# 3_-STM32F103_Debugger.net
KiCad netlist of a schematic drawn in Altium Designer
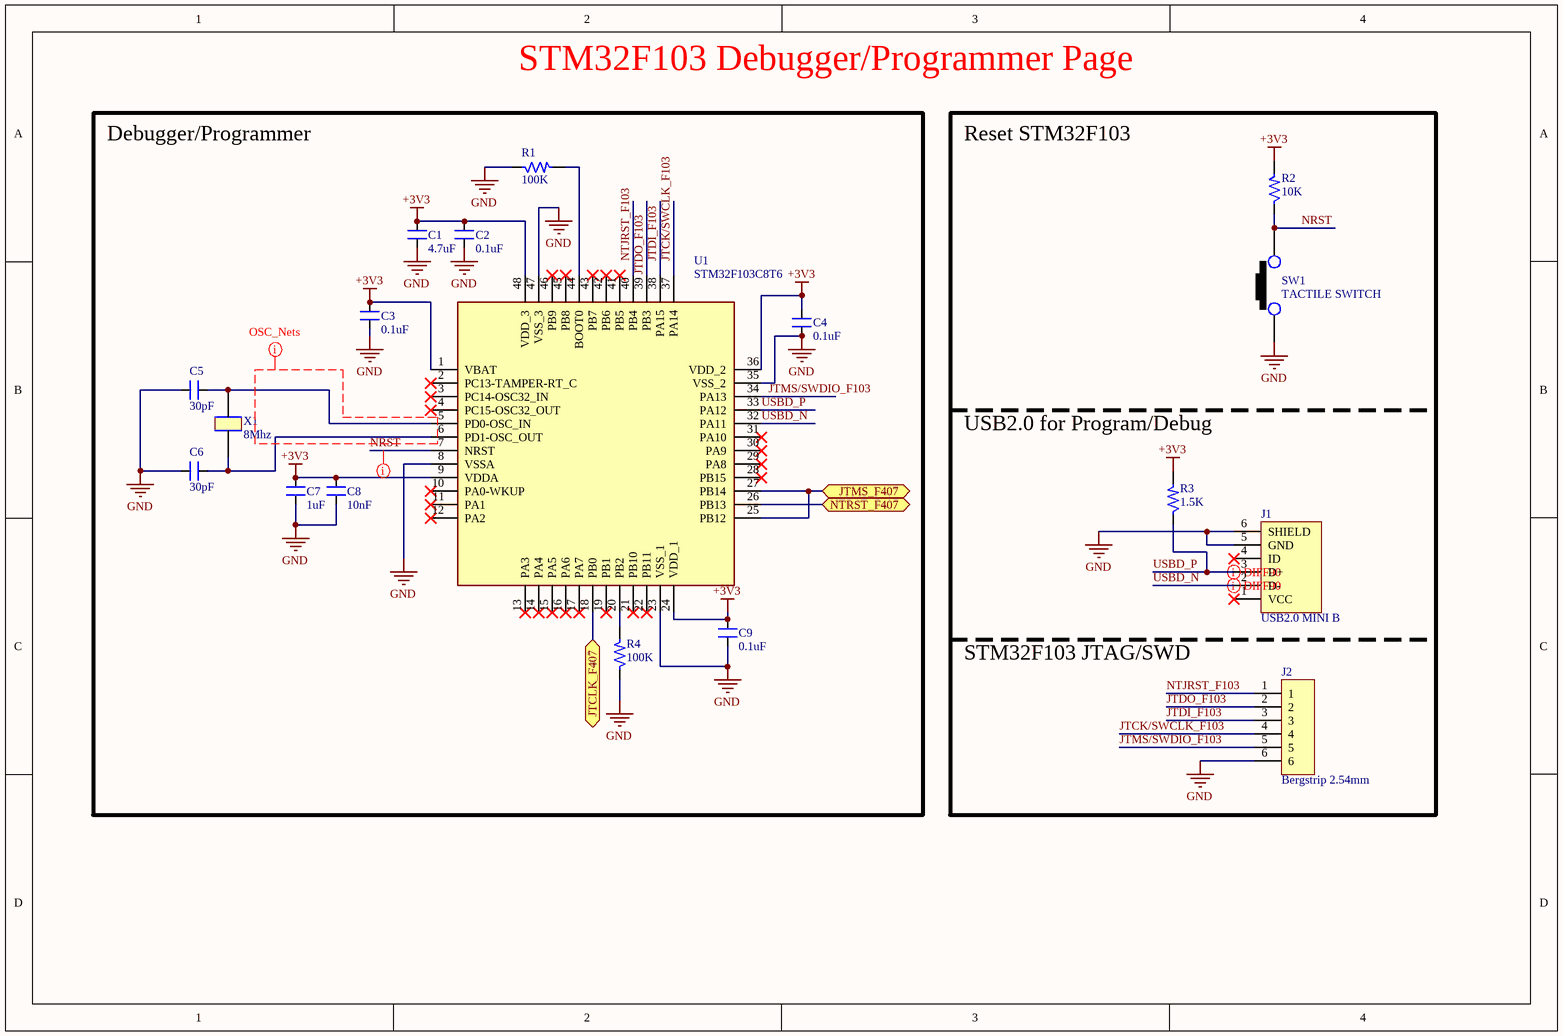
[diagram p0: [3]-STM32F103 Debugger.SchDoc]

(export (version "E")
  (design (tool "Eeschema 10.0.6"))
  (components
    (comp (ref "C1")
      (value "4.7uF")
      (footprint "CAP_0805")
      (description "4.7µF ±10% 50V Ceramic Capacitor X5R 0805 (2012 Metric)")
      (fields
        (field (name "MANUFACTURER") "Yageo")
        (field (name "MANUFACTURER PART NUMBER") "GRM21BR61H475KE51L")
      )
      (libsource (lib "ESTEEMPCBLIB") (part "CAP_4.7uF-50V-10%-0805"))
    )
    (comp (ref "C2")
      (value "0.1uF")
      (footprint "CAP_0805")
      (description "0.1µF ±10% 50V Ceramic Capacitor X7R 0805 (2012 Metric)")
      (fields
        (field (name "MANUFACTURER") "Samsung")
        (field (name "MANUFACTURER PART NUMBER") "CL21B104KBCNNNC")
      )
      (libsource (lib "ESTEEMPCBLIB") (part "CAP_0.1uF-50V-10%-0805"))
    )
    (comp (ref "C3")
      (value "0.1uF")
      (footprint "CAP_0805")
      (description "0.1µF ±10% 50V Ceramic Capacitor X7R 0805 (2012 Metric)")
      (fields
        (field (name "MANUFACTURER") "Samsung")
        (field (name "MANUFACTURER PART NUMBER") "CL21B104KBCNNNC")
      )
      (libsource (lib "ESTEEMPCBLIB") (part "CAP_0.1uF-50V-10%-0805"))
    )
    (comp (ref "C4")
      (value "0.1uF")
      (footprint "CAP_0805")
      (description "0.1µF ±10% 50V Ceramic Capacitor X7R 0805 (2012 Metric)")
      (fields
        (field (name "MANUFACTURER") "Samsung")
        (field (name "MANUFACTURER PART NUMBER") "CL21B104KBCNNNC")
      )
      (libsource (lib "ESTEEMPCBLIB") (part "CAP_0.1uF-50V-10%-0805"))
    )
    (comp (ref "C5")
      (value "30pF")
      (footprint "CAP_0805")
      (description "±10% 50V Ceramic Capacitor C0G, NP0 0805 (2012 Metric)")
      (fields
        (field (name "MANUFACTURER PART NUMBER") "C0805C300K5GAC7800")
        (field (name "MANUFACTURER") "KEMET")
      )
      (libsource (lib "ESTEEMPCBLIB") (part "CAP_30pF-50V-10%-0805"))
    )
    (comp (ref "C6")
      (value "30pF")
      (footprint "CAP_0805")
      (description "±10% 50V Ceramic Capacitor C0G, NP0 0805 (2012 Metric)")
      (fields
        (field (name "MANUFACTURER PART NUMBER") "C0805C300K5GAC7800")
        (field (name "MANUFACTURER") "KEMET")
      )
      (libsource (lib "ESTEEMPCBLIB") (part "CAP_30pF-50V-10%-0805"))
    )
    (comp (ref "C7")
      (value "1uF")
      (footprint "CAP_0805")
      (description "1µF ±5% 50V Ceramic Capacitor X7R 0805 (2012 Metric)")
      (fields
        (field (name "MANUFACTURER") "Samsung")
        (field (name "MANUFACTURER PART NUMBER") "CC0805JKX7R9BB105")
      )
      (libsource (lib "ESTEEMPCBLIB") (part "CAP_1uF-50V-5%-0805"))
    )
    (comp (ref "C8")
      (value "10nF")
      (footprint "CAP_0805")
      (description "10000pF ±10% 50V Ceramic Capacitor X7R 0805 (2012 Metric)")
      (fields
        (field (name "MANUFACTURER") "Samsung")
        (field (name "MANUFACTURER PART NUMBER") "C0805C103K5RECAUTO")
      )
      (libsource (lib "ESTEEMPCBLIB") (part "CAP_10nF-50V-10%-0805"))
    )
    (comp (ref "C9")
      (value "0.1uF")
      (footprint "CAP_0805")
      (description "0.1µF ±10% 50V Ceramic Capacitor X7R 0805 (2012 Metric)")
      (fields
        (field (name "MANUFACTURER") "Samsung")
        (field (name "MANUFACTURER PART NUMBER") "CL21B104KBCNNNC")
      )
      (libsource (lib "ESTEEMPCBLIB") (part "CAP_0.1uF-50V-10%-0805"))
    )
    (comp (ref "J1")
      (value "USB2.0 MINI B")
      (footprint "CON_690-005-299-043")
      (description "USB - mini B USB 2.0 Receptacle Connector 5 Position Surface Mount, Right Angle")
      (fields
        (field (name "MANUFACTURER") "EDAC")
        (field (name "MANUFACTURER PART NUMBER") "690-005-299-043")
      )
      (libsource (lib "ESTEEMPCBLIB") (part "CON_USB2.0-MINIB-SMD"))
    )
    (comp (ref "J2")
      (value "Bergstrip 2.54mm")
      (footprint "CON6_100_59D78_TH_ST")
      (description "6 Pins, 1 Row 2.54mm Pitch, Straight bergstrip, Female")
      (fields (field (name "MANUFACTURER") "Molex") (field (name "MANUFACTURER PART NUMBER") "22-10-2061"))
      (libsource (lib "ESTEEMPCBLIB") (part "CON-BS-SKT_6X1-100-ST-TH"))
    )
    (comp (ref "R1")
      (value "100K")
      (footprint "RES_0603")
      (description "100 kOhms ±1% 0.1W, 1/10W Chip Resistor 0603 (1608 Metric) Automotive AEC-Q200 Thick Film")
      (fields
        (field (name "MANUFACTURER") "Stackpole Electronics")
        (field (name "MANUFACTURER PART NUMBER") "RMCF0603FT100K")
      )
      (libsource (lib "ESTEEMPCBLIB") (part "RES_100K-0.1W-1%-0603"))
    )
    (comp (ref "R2")
      (value "10K")
      (footprint "RES_0603")
      (description "10 kOhms ±1% 0.1W, 1/10W Chip Resistor 0603 (1608 Metric) Automotive AEC-Q200 Thick Film")
      (fields (field (name "MANUFACTURER") "Walsin") (field (name "MANUFACTURER PART NUMBER") "WR06X1002FTL"))
      (libsource (lib "ESTEEMPCBLIB") (part "RES_10K-0.1W-1%-0603"))
    )
    (comp (ref "R3")
      (value "1.5K")
      (footprint "RES_0805")
      (description "1.5 kOhms ±1% 0.125W, 1/8W Chip Resistor 0805 (2012 Metric) Thick Film")
      (fields
        (field (name "MANUFACTURER") "TE Connectivity Passive Product")
        (field (name "MANUFACTURER PART NUMBER") "CRG0805F1K5")
      )
      (libsource (lib "ESTEEMPCBLIB") (part "RES_1.5K-0.125W-1%-0805"))
    )
    (comp (ref "R4")
      (value "100K")
      (footprint "RES_0603")
      (description "100 kOhms ±1% 0.1W, 1/10W Chip Resistor 0603 (1608 Metric) Automotive AEC-Q200 Thick Film")
      (fields
        (field (name "MANUFACTURER") "Stackpole Electronics")
        (field (name "MANUFACTURER PART NUMBER") "RMCF0603FT100K")
      )
      (libsource (lib "ESTEEMPCBLIB") (part "RES_100K-0.1W-1%-0603"))
    )
    (comp (ref "SW1")
      (value "TACTILE SWITCH")
      (footprint "SW_342_SMD")
      (description "Tactile Switch SPST-NO Top Actuated Surface Mount")
      (fields
        (field (name "MANUFACTURER") "ITT C&K")
        (field (name "MANUFACTURER PART NUMBER") "RS-282G05A3-SMRT")
      )
      (libsource (lib "ESTEEMPCBLIB") (part "SW1_RS-282G05A3-SMRT-SMD"))
    )
    (comp (ref "U1")
      (value "STM32F103C8T6")
      (footprint "LQFP-48_19.6_393_58X11_SMD")
      (description "ARM® Cortex®-M3 STM32F1 Microcontroller IC 32-Bit 72MHz 64KB (64K x 8) FLASH 48-LQFP (7x7)")
      (fields (field (name "MANUFACTURER") "STMicroelectronics"))
      (libsource (lib "ESTEEMPCBLIB") (part "IC_STM32F103C8T6"))
    )
    (comp (ref "X1")
      (value "8Mhz")
      (footprint "XTAL_314_240X47_SMD")
      (description "8MHz ±30ppm Crystal 32pF 60 Ohms HC-49/US")
      (fields
        (field (name "MANUFACTURER") "Fox Electronics")
        (field (name "MANUFACTURER PART NUMBER") "ECS-80-32-5PX-TR")
      )
      (libsource (lib "ESTEEMPCBLIB") (part "XTAL_8MHZ-ECS-80-32-5PX-SMD"))
    )
  )
  (nets
    (net (code "1") (name "+3V3") (class "Default")
      (node (ref "C1") (pin "2") (pinfunction "2_2") (pintype "passive"))
      (node (ref "C2") (pin "2") (pinfunction "2_2") (pintype "passive"))
      (node (ref "C3") (pin "2") (pinfunction "2_2") (pintype "passive"))
      (node (ref "C4") (pin "2") (pinfunction "2_2") (pintype "passive"))
      (node (ref "C7") (pin "2") (pinfunction "2_2") (pintype "passive"))
      (node (ref "C8") (pin "2") (pinfunction "2_2") (pintype "passive"))
      (node (ref "C9") (pin "2") (pinfunction "2_2") (pintype "passive"))
      (node (ref "R2") (pin "2") (pinfunction "2_2") (pintype "passive"))
      (node (ref "R3") (pin "2") (pinfunction "2_2") (pintype "passive"))
      (node (ref "U1") (pin "1") (pinfunction "VBAT_1") (pintype "passive"))
      (node (ref "U1") (pin "24") (pinfunction "VDD_1_24") (pintype "passive"))
      (node (ref "U1") (pin "36") (pinfunction "VDD_2_36") (pintype "passive"))
      (node (ref "U1") (pin "48") (pinfunction "VDD_3_48") (pintype "passive"))
      (node (ref "U1") (pin "9") (pinfunction "VDDA_9") (pintype "passive"))
    )
    (net (code "2") (name "/JTCK{slash}SWCLK_F103") (class "Default")
      (node (ref "J2") (pin "4") (pinfunction "4_4") (pintype "passive"))
      (node (ref "U1") (pin "37") (pinfunction "PA14_37") (pintype "passive"))
    )
    (net (code "3") (name "/JTCLK_F407") (class "Default")
      (node (ref "U1") (pin "18") (pinfunction "PB0_18") (pintype "passive"))
    )
    (net (code "4") (name "/JTDI_F103") (class "Default")
      (node (ref "J2") (pin "3") (pinfunction "3_3") (pintype "passive"))
      (node (ref "U1") (pin "38") (pinfunction "PA15_38") (pintype "passive"))
    )
    (net (code "5") (name "/JTDO_F103") (class "Default")
      (node (ref "J2") (pin "2") (pinfunction "2_2") (pintype "passive"))
      (node (ref "U1") (pin "39") (pinfunction "PB3_39") (pintype "passive"))
    )
    (net (code "6") (name "/JTMS_F407") (class "Default")
      (node (ref "U1") (pin "25") (pinfunction "PB12_25") (pintype "passive"))
      (node (ref "U1") (pin "27") (pinfunction "PB14_27") (pintype "passive"))
    )
    (net (code "7") (name "/JTMS{slash}SWDIO_F103") (class "Default")
      (node (ref "J2") (pin "5") (pinfunction "5_5") (pintype "passive"))
      (node (ref "U1") (pin "34") (pinfunction "PA13_34") (pintype "passive"))
    )
    (net (code "8") (name "/NRST") (class "Default")
      (node (ref "R2") (pin "1") (pinfunction "1_1") (pintype "passive"))
      (node (ref "SW1") (pin "2") (pinfunction "2_2") (pintype "passive"))
      (node (ref "U1") (pin "7") (pinfunction "NRST_7") (pintype "passive"))
    )
    (net (code "9") (name "/NTJRST_F103") (class "Default")
      (node (ref "J2") (pin "1") (pinfunction "1_1") (pintype "passive"))
      (node (ref "U1") (pin "40") (pinfunction "PB4_40") (pintype "passive"))
    )
    (net (code "10") (name "/NTRST_F407") (class "Default")
      (node (ref "U1") (pin "26") (pinfunction "PB13_26") (pintype "passive"))
    )
    (net (code "11") (name "/USBD_N") (class "Default")
      (node (ref "J1") (pin "2") (pinfunction "D-_2") (pintype "passive"))
      (node (ref "U1") (pin "32") (pinfunction "PA11_32") (pintype "passive"))
    )
    (net (code "12") (name "/USBD_P") (class "Default")
      (node (ref "J1") (pin "3") (pinfunction "D+_3") (pintype "passive"))
      (node (ref "R3") (pin "1") (pinfunction "1_1") (pintype "passive"))
      (node (ref "U1") (pin "33") (pinfunction "PA12_33") (pintype "passive"))
    )
    (net (code "13") (name "GND") (class "Default")
      (node (ref "C1") (pin "1") (pinfunction "1_1") (pintype "passive"))
      (node (ref "C2") (pin "1") (pinfunction "1_1") (pintype "passive"))
      (node (ref "C3") (pin "1") (pinfunction "1_1") (pintype "passive"))
      (node (ref "C4") (pin "1") (pinfunction "1_1") (pintype "passive"))
      (node (ref "C5") (pin "1") (pinfunction "1_1") (pintype "passive"))
      (node (ref "C6") (pin "1") (pinfunction "1_1") (pintype "passive"))
      (node (ref "C7") (pin "1") (pinfunction "1_1") (pintype "passive"))
      (node (ref "C8") (pin "1") (pinfunction "1_1") (pintype "passive"))
      (node (ref "C9") (pin "1") (pinfunction "1_1") (pintype "passive"))
      (node (ref "J1") (pin "5") (pinfunction "GND_5") (pintype "passive"))
      (node (ref "J1") (pin "6") (pinfunction "SHIELD_6") (pintype "passive"))
      (node (ref "J2") (pin "6") (pinfunction "6_6") (pintype "passive"))
      (node (ref "R1") (pin "1") (pinfunction "1_1") (pintype "passive"))
      (node (ref "R4") (pin "1") (pinfunction "1_1") (pintype "passive"))
      (node (ref "SW1") (pin "1") (pinfunction "1_1") (pintype "passive"))
      (node (ref "U1") (pin "23") (pinfunction "VSS_1_23") (pintype "passive"))
      (node (ref "U1") (pin "35") (pinfunction "VSS_2_35") (pintype "passive"))
      (node (ref "U1") (pin "47") (pinfunction "VSS_3_47") (pintype "passive"))
      (node (ref "U1") (pin "8") (pinfunction "VSSA_8") (pintype "passive"))
    )
    (net (code "14") (name "Net-(U1-BOOT0)") (class "Default")
      (node (ref "R1") (pin "2") (pinfunction "2_2") (pintype "passive"))
      (node (ref "U1") (pin "44") (pinfunction "BOOT0_44") (pintype "passive"))
    )
    (net (code "15") (name "Net-(U1-PB2)") (class "Default")
      (node (ref "R4") (pin "2") (pinfunction "2_2") (pintype "passive"))
      (node (ref "U1") (pin "20") (pinfunction "PB2_20") (pintype "passive"))
    )
    (net (code "16") (name "Net-(U1-PD0-OSC_IN)") (class "Default")
      (node (ref "C5") (pin "2") (pinfunction "2_2") (pintype "passive"))
      (node (ref "U1") (pin "5") (pinfunction "PD0-OSC_IN_5") (pintype "passive"))
      (node (ref "X1") (pin "2") (pinfunction "2_2") (pintype "passive"))
    )
    (net (code "17") (name "Net-(U1-PD1-OSC_OUT)") (class "Default")
      (node (ref "C6") (pin "2") (pinfunction "2_2") (pintype "passive"))
      (node (ref "U1") (pin "6") (pinfunction "PD1-OSC_OUT_6") (pintype "passive"))
      (node (ref "X1") (pin "1") (pinfunction "1_1") (pintype "passive"))
    )
    (net (code "18") (name "unconnected-(J1-ID-Pad4)") (class "Default")
      (node (ref "J1") (pin "4") (pinfunction "ID_4") (pintype "passive+no_connect"))
    )
    (net (code "19") (name "unconnected-(J1-VCC-Pad1)") (class "Default")
      (node (ref "J1") (pin "1") (pinfunction "VCC_1") (pintype "passive+no_connect"))
    )
    (net (code "20") (name "unconnected-(U1-PA0-WKUP-Pad10)") (class "Default")
      (node (ref "U1") (pin "10") (pinfunction "PA0-WKUP_10") (pintype "passive+no_connect"))
    )
    (net (code "21") (name "unconnected-(U1-PA1-Pad11)") (class "Default")
      (node (ref "U1") (pin "11") (pinfunction "PA1_11") (pintype "passive+no_connect"))
    )
    (net (code "22") (name "unconnected-(U1-PA2-Pad12)") (class "Default")
      (node (ref "U1") (pin "12") (pinfunction "PA2_12") (pintype "passive+no_connect"))
    )
    (net (code "23") (name "unconnected-(U1-PA3-Pad13)") (class "Default")
      (node (ref "U1") (pin "13") (pinfunction "PA3_13") (pintype "passive+no_connect"))
    )
    (net (code "24") (name "unconnected-(U1-PA4-Pad14)") (class "Default")
      (node (ref "U1") (pin "14") (pinfunction "PA4_14") (pintype "passive+no_connect"))
    )
    (net (code "25") (name "unconnected-(U1-PA5-Pad15)") (class "Default")
      (node (ref "U1") (pin "15") (pinfunction "PA5_15") (pintype "passive+no_connect"))
    )
    (net (code "26") (name "unconnected-(U1-PA6-Pad16)") (class "Default")
      (node (ref "U1") (pin "16") (pinfunction "PA6_16") (pintype "passive+no_connect"))
    )
    (net (code "27") (name "unconnected-(U1-PA7-Pad17)") (class "Default")
      (node (ref "U1") (pin "17") (pinfunction "PA7_17") (pintype "passive+no_connect"))
    )
    (net (code "28") (name "unconnected-(U1-PA8-Pad29)") (class "Default")
      (node (ref "U1") (pin "29") (pinfunction "PA8_29") (pintype "passive+no_connect"))
    )
    (net (code "29") (name "unconnected-(U1-PA9-Pad30)") (class "Default")
      (node (ref "U1") (pin "30") (pinfunction "PA9_30") (pintype "passive+no_connect"))
    )
    (net (code "30") (name "unconnected-(U1-PA10-Pad31)") (class "Default")
      (node (ref "U1") (pin "31") (pinfunction "PA10_31") (pintype "passive+no_connect"))
    )
    (net (code "31") (name "unconnected-(U1-PB1-Pad19)") (class "Default")
      (node (ref "U1") (pin "19") (pinfunction "PB1_19") (pintype "passive+no_connect"))
    )
    (net (code "32") (name "unconnected-(U1-PB5-Pad41)") (class "Default")
      (node (ref "U1") (pin "41") (pinfunction "PB5_41") (pintype "passive+no_connect"))
    )
    (net (code "33") (name "unconnected-(U1-PB6-Pad42)") (class "Default")
      (node (ref "U1") (pin "42") (pinfunction "PB6_42") (pintype "passive+no_connect"))
    )
    (net (code "34") (name "unconnected-(U1-PB7-Pad43)") (class "Default")
      (node (ref "U1") (pin "43") (pinfunction "PB7_43") (pintype "passive+no_connect"))
    )
    (net (code "35") (name "unconnected-(U1-PB8-Pad45)") (class "Default")
      (node (ref "U1") (pin "45") (pinfunction "PB8_45") (pintype "passive+no_connect"))
    )
    (net (code "36") (name "unconnected-(U1-PB9-Pad46)") (class "Default")
      (node (ref "U1") (pin "46") (pinfunction "PB9_46") (pintype "passive+no_connect"))
    )
    (net (code "37") (name "unconnected-(U1-PB10-Pad21)") (class "Default")
      (node (ref "U1") (pin "21") (pinfunction "PB10_21") (pintype "passive+no_connect"))
    )
    (net (code "38") (name "unconnected-(U1-PB11-Pad22)") (class "Default")
      (node (ref "U1") (pin "22") (pinfunction "PB11_22") (pintype "passive+no_connect"))
    )
    (net (code "39") (name "unconnected-(U1-PB15-Pad28)") (class "Default")
      (node (ref "U1") (pin "28") (pinfunction "PB15_28") (pintype "passive+no_connect"))
    )
    (net (code "40") (name "unconnected-(U1-PC13-TAMPER-RT_C-Pad2)") (class "Default")
      (node (ref "U1") (pin "2") (pinfunction "PC13-TAMPER-RT_C_2") (pintype "passive+no_connect"))
    )
    (net (code "41") (name "unconnected-(U1-PC14-OSC32_IN-Pad3)") (class "Default")
      (node (ref "U1") (pin "3") (pinfunction "PC14-OSC32_IN_3") (pintype "passive+no_connect"))
    )
    (net (code "42") (name "unconnected-(U1-PC15-OSC32_OUT-Pad4)") (class "Default")
      (node (ref "U1") (pin "4") (pinfunction "PC15-OSC32_OUT_4") (pintype "passive+no_connect"))
    )
  )
)
